# 09_USB_Bridge.net
KiCad netlist of a schematic drawn in Altium Designer
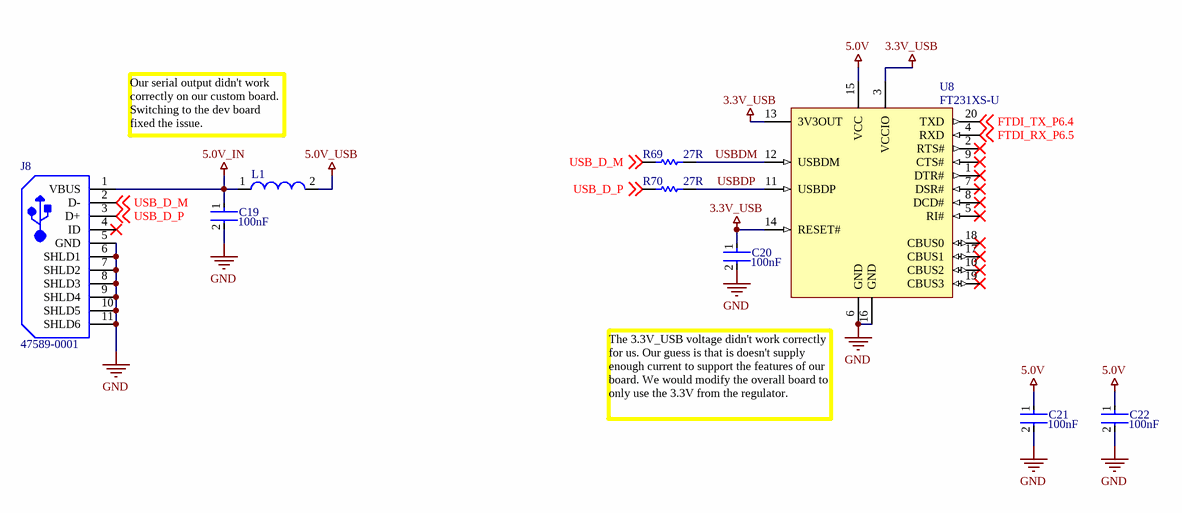
[diagram p0: 09_USB_Bridge.SchDoc]

(export (version "E")
  (design (tool "Eeschema 10.0.6"))
  (components
    (comp (ref "C19")
      (value "100nF")
      (footprint "FP-C0805C-DN-MFG")
      (description "CAP CER 0.1UF 50V X7R 0805")
      (fields
        (field (name "MANUFACTURER") "KEMET")
        (field (name "MANUFACTURER PART NUMBER") "C0805C104K5RACTU")
      )
      (libsource (lib "Altium Content Vault") (part "b4654b650e69147ec39a6b967a45e02"))
    )
    (comp (ref "C20")
      (value "100nF")
      (footprint "FP-C0805C-DN-MFG")
      (description "CAP CER 0.1UF 50V X7R 0805")
      (fields
        (field (name "MANUFACTURER") "KEMET")
        (field (name "MANUFACTURER PART NUMBER") "C0805C104K5RACTU")
      )
      (libsource (lib "Altium Content Vault") (part "b4654b650e69147ec39a6b967a45e02"))
    )
    (comp (ref "C21")
      (value "100nF")
      (footprint "FP-C0805C-DN-MFG")
      (description "CAP CER 0.1UF 50V X7R 0805")
      (fields
        (field (name "MANUFACTURER") "KEMET")
        (field (name "MANUFACTURER PART NUMBER") "C0805C104K5RACTU")
      )
      (libsource (lib "Altium Content Vault") (part "b4654b650e69147ec39a6b967a45e02"))
    )
    (comp (ref "C22")
      (value "100nF")
      (footprint "FP-C0805C-DN-MFG")
      (description "CAP CER 0.1UF 50V X7R 0805")
      (fields
        (field (name "MANUFACTURER") "KEMET")
        (field (name "MANUFACTURER PART NUMBER") "C0805C104K5RACTU")
      )
      (libsource (lib "Altium Content Vault") (part "b4654b650e69147ec39a6b967a45e02"))
    )
    (comp (ref "J8")
      (value "47589-0001")
      (footprint "MOLX-47589-0001_V")
      (description "Right Angle Female Type AB Micro USB Connector, 30 V, 1.8 A, -30 to 85 degC, RoHS, Tape and Reel")
      (fields (field (name "MANUFACTURER") "Molex"))
      (libsource (lib "Altium Content Vault") (part "USB-5-6SHLD"))
    )
    (comp (ref "L1")
      (value "742792093")
      (footprint "SMD-0805")
      (description "SMD EMI Suppression Ferrite Bead WE-CBF, Z = 2200 Ohm")
      (fields (field (name "MANUFACTURER") "Wurth Electronics") (field (name "TOLERANCE") "25%"))
      (libsource (lib "Altium Content Vault") (part "PAS-IND-INDUCTOR-2"))
    )
    (comp (ref "R69")
      (value "27R")
      (footprint "RESC2013X70X40ML20T20")
      (fields
        (field (name "MANUFACTURER") "Vishay")
        (field (name "MANUFACTURER PART NUMBER") "CRCW080527R0FKEAHP")
        (field (name "TOLERANCE") "1%")
      )
      (libsource (lib "Altium Content Vault") (part "RES"))
    )
    (comp (ref "R70")
      (value "27R")
      (footprint "RESC2013X70X40ML20T20")
      (fields
        (field (name "MANUFACTURER") "Vishay")
        (field (name "MANUFACTURER PART NUMBER") "CRCW080527R0FKEAHP")
        (field (name "TOLERANCE") "1%")
      )
      (libsource (lib "Altium Content Vault") (part "RES"))
    )
    (comp (ref "U8")
      (value "FT231XS-U")
      (footprint "SSOP-20_L")
      (fields (field (name "MANUFACTURER") "FTDI") (field (name "MANUFACTURER PART NUMBER") "FT231XS-R"))
      (libsource (lib "Altium Content Vault") (part "COM-USB-FT231XS-IL20"))
    )
  )
  (nets
    (net (code "1") (name "/USBDM") (class "Default")
      (node (ref "R69") (pin "2") (pinfunction "2_2") (pintype "passive"))
      (node (ref "U8") (pin "12") (pinfunction "USBDM_12") (pintype "input"))
    )
    (net (code "2") (name "/USBDP") (class "Default")
      (node (ref "R70") (pin "2") (pinfunction "2_2") (pintype "passive"))
      (node (ref "U8") (pin "11") (pinfunction "USBDP_11") (pintype "input"))
    )
    (net (code "3") (name "3.3V_USB") (class "Default")
      (node (ref "C20") (pin "1") (pinfunction "1_1") (pintype "passive"))
      (node (ref "U8") (pin "13") (pinfunction "3V3OUT_13") (pintype "power_in"))
      (node (ref "U8") (pin "14") (pinfunction "RESET#_14") (pintype "input"))
      (node (ref "U8") (pin "3") (pinfunction "VCCIO_3") (pintype "power_in"))
    )
    (net (code "4") (name "5.0V") (class "Default")
      (node (ref "C21") (pin "1") (pinfunction "1_1") (pintype "passive"))
      (node (ref "C22") (pin "1") (pinfunction "1_1") (pintype "passive"))
      (node (ref "U8") (pin "15") (pinfunction "VCC_15") (pintype "power_in"))
    )
    (net (code "5") (name "5.0V_IN") (class "Default")
      (node (ref "C19") (pin "1") (pinfunction "1_1") (pintype "passive"))
      (node (ref "J8") (pin "1") (pinfunction "VBUS_1") (pintype "passive"))
      (node (ref "L1") (pin "1") (pinfunction "1_1") (pintype "passive"))
    )
    (net (code "6") (name "5.0V_USB") (class "Default")
      (node (ref "L1") (pin "2") (pinfunction "2_2") (pintype "passive"))
    )
    (net (code "7") (name "FTDI_RX_P6.5") (class "Default")
      (node (ref "U8") (pin "4") (pinfunction "RXD_4") (pintype "input"))
    )
    (net (code "8") (name "FTDI_TX_P6.4") (class "Default")
      (node (ref "U8") (pin "20") (pinfunction "TXD_20") (pintype "output"))
    )
    (net (code "9") (name "GND") (class "Default")
      (node (ref "C19") (pin "2") (pinfunction "2_2") (pintype "passive"))
      (node (ref "C20") (pin "2") (pinfunction "2_2") (pintype "passive"))
      (node (ref "C21") (pin "2") (pinfunction "2_2") (pintype "passive"))
      (node (ref "C22") (pin "2") (pinfunction "2_2") (pintype "passive"))
      (node (ref "J8") (pin "10") (pinfunction "SHLD5_10") (pintype "passive"))
      (node (ref "J8") (pin "11") (pinfunction "SHLD6_11") (pintype "passive"))
      (node (ref "J8") (pin "5") (pinfunction "GND_5") (pintype "passive"))
      (node (ref "J8") (pin "6") (pinfunction "SHLD1_6") (pintype "passive"))
      (node (ref "J8") (pin "7") (pinfunction "SHLD2_7") (pintype "passive"))
      (node (ref "J8") (pin "8") (pinfunction "SHLD3_8") (pintype "passive"))
      (node (ref "J8") (pin "9") (pinfunction "SHLD4_9") (pintype "passive"))
      (node (ref "U8") (pin "16") (pinfunction "GND_16") (pintype "power_in"))
      (node (ref "U8") (pin "6") (pinfunction "GND_6") (pintype "power_in"))
    )
    (net (code "10") (name "USB_D_M") (class "Default")
      (node (ref "J8") (pin "2") (pinfunction "D-_2") (pintype "passive"))
      (node (ref "R69") (pin "1") (pinfunction "1_1") (pintype "passive"))
    )
    (net (code "11") (name "USB_D_P") (class "Default")
      (node (ref "J8") (pin "3") (pinfunction "D+_3") (pintype "passive"))
      (node (ref "R70") (pin "1") (pinfunction "1_1") (pintype "passive"))
    )
    (net (code "12") (name "unconnected-(J8-ID-Pad4)") (class "Default")
      (node (ref "J8") (pin "4") (pinfunction "ID_4") (pintype "passive+no_connect"))
    )
    (net (code "13") (name "unconnected-(U8-CBUS0-Pad18)") (class "Default")
      (node (ref "U8") (pin "18") (pinfunction "CBUS0_18") (pintype "bidirectional+no_connect"))
    )
    (net (code "14") (name "unconnected-(U8-CBUS1-Pad17)") (class "Default")
      (node (ref "U8") (pin "17") (pinfunction "CBUS1_17") (pintype "bidirectional+no_connect"))
    )
    (net (code "15") (name "unconnected-(U8-CBUS2-Pad10)") (class "Default")
      (node (ref "U8") (pin "10") (pinfunction "CBUS2_10") (pintype "bidirectional+no_connect"))
    )
    (net (code "16") (name "unconnected-(U8-CBUS3-Pad19)") (class "Default")
      (node (ref "U8") (pin "19") (pinfunction "CBUS3_19") (pintype "bidirectional+no_connect"))
    )
    (net (code "17") (name "unconnected-(U8-CTS#-Pad9)") (class "Default")
      (node (ref "U8") (pin "9") (pinfunction "CTS#_9") (pintype "input+no_connect"))
    )
    (net (code "18") (name "unconnected-(U8-DCD#-Pad8)") (class "Default")
      (node (ref "U8") (pin "8") (pinfunction "DCD#_8") (pintype "input+no_connect"))
    )
    (net (code "19") (name "unconnected-(U8-DSR#-Pad7)") (class "Default")
      (node (ref "U8") (pin "7") (pinfunction "DSR#_7") (pintype "input+no_connect"))
    )
    (net (code "20") (name "unconnected-(U8-DTR#-Pad1)") (class "Default")
      (node (ref "U8") (pin "1") (pinfunction "DTR#_1") (pintype "output+no_connect"))
    )
    (net (code "21") (name "unconnected-(U8-RI#-Pad5)") (class "Default")
      (node (ref "U8") (pin "5") (pinfunction "RI#_5") (pintype "input+no_connect"))
    )
    (net (code "22") (name "unconnected-(U8-RTS#-Pad2)") (class "Default")
      (node (ref "U8") (pin "2") (pinfunction "RTS#_2") (pintype "output+no_connect"))
    )
  )
)
